# Buck_Converter.net
KiCad netlist of a schematic drawn in Altium Designer
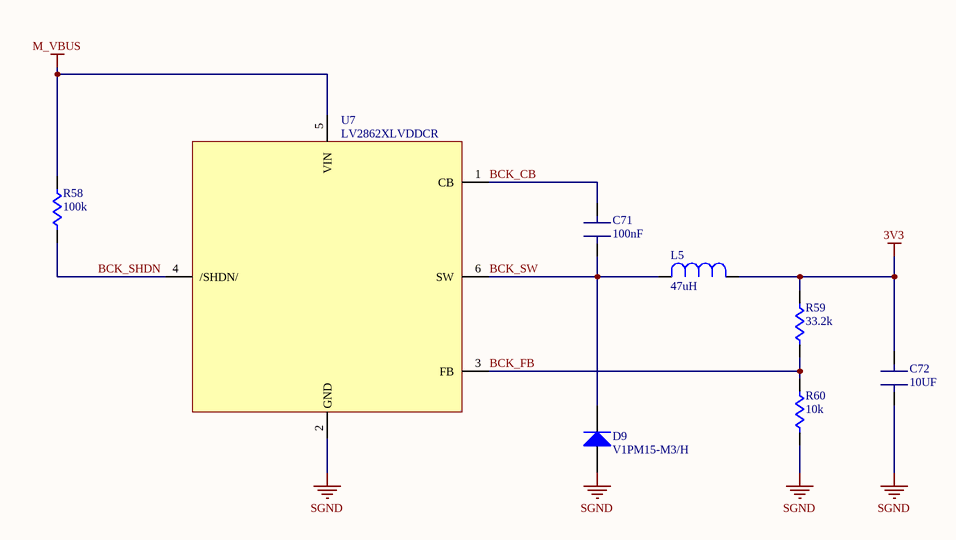
[diagram p0: Buck_Converter.SchDoc]

(export (version "E")
  (design (tool "Eeschema 10.0.6"))
  (components
    (comp (ref "C71")
      (value "100nF")
      (footprint "CAP: 0603")
      (description "CAP SMD 0603")
      (libsource (lib "HZSchLib") (part "CAP 0603"))
    )
    (comp (ref "C72")
      (value "10UF")
      (footprint "CAP: 0805")
      (description "CAP SMD 0805")
      (libsource (lib "HZSchLib") (part "CAP 0805"))
    )
    (comp (ref "D9")
      (value "V1PM15-M3/H")
      (footprint "DO-219AD-2")
      (description "Schottky Diodes & Rectifiers 150V 1A TMBS MicroSMP")
      (libsource (lib "HZSchLib") (part "V1PM15-M3/H"))
    )
    (comp (ref "L5")
      (value "47uH")
      (footprint "MDH6045C")
      (description "Power Inductors - SMD 47uH 208mOhms 20 % 1A AEC-Q200")
      (libsource (lib "HZSchLib") (part "MDH6045C-470MA=P3"))
    )
    (comp (ref "R58")
      (value "100k")
      (footprint "RES: 0603")
      (description "RES SMD 0603")
      (libsource (lib "HZSchLib") (part "RES 0603"))
    )
    (comp (ref "R59")
      (value "33.2k")
      (footprint "RES: 0603")
      (description "RES SMD 0603")
      (libsource (lib "HZSchLib") (part "RES 0603"))
    )
    (comp (ref "R60")
      (value "10k")
      (footprint "RES: 0603")
      (description "RES SMD 0603")
      (libsource (lib "HZSchLib") (part "RES 0603"))
    )
    (comp (ref "U7")
      (value "LV2862XLVDDCR")
      (footprint "SOT23-6")
      (description "Switching Voltage Regulators 4.5-V to 60-V 600-m A buck converter in A 595-LV2862XLVDDCT")
      (libsource (lib "HZSchLib") (part "LV2862XLVDDCR"))
    )
  )
  (nets
    (net (code "2") (name "/BCK_CB") (class "Default")
      (node (ref "C71") (pin "2") (pinfunction "B_2") (pintype "passive"))
      (node (ref "U7") (pin "1") (pinfunction "CB_1") (pintype "passive"))
    )
    (net (code "3") (name "/BCK_FB") (class "Default")
      (node (ref "R59") (pin "1") (pinfunction "1_1") (pintype "passive"))
      (node (ref "R60") (pin "2") (pinfunction "2_2") (pintype "passive"))
      (node (ref "U7") (pin "3") (pinfunction "FB_3") (pintype "passive"))
    )
    (net (code "4") (name "/BCK_SHDN") (class "Default")
      (node (ref "R58") (pin "1") (pinfunction "1_1") (pintype "passive"))
      (node (ref "U7") (pin "4") (pinfunction "/SHDN/_4") (pintype "power_in"))
    )
    (net (code "5") (name "/BCK_SW") (class "Default")
      (node (ref "C71") (pin "1") (pinfunction "A_1") (pintype "passive"))
      (node (ref "D9") (pin "1") (pinfunction "K_1") (pintype "passive"))
      (node (ref "L5") (pin "1") (pinfunction "1_1") (pintype "passive"))
      (node (ref "U7") (pin "6") (pinfunction "SW_6") (pintype "passive"))
    )
    (net (code "6") (name "3V3") (class "Default")
      (node (ref "C72") (pin "2") (pinfunction "B_2") (pintype "passive"))
      (node (ref "L5") (pin "2") (pinfunction "2_2") (pintype "passive"))
      (node (ref "R59") (pin "2") (pinfunction "2_2") (pintype "passive"))
    )
    (net (code "7") (name "M_VBUS") (class "Default")
      (node (ref "R58") (pin "2") (pinfunction "2_2") (pintype "passive"))
      (node (ref "U7") (pin "5") (pinfunction "VIN_5") (pintype "passive"))
    )
    (net (code "8") (name "SGND") (class "Default")
      (node (ref "C72") (pin "1") (pinfunction "A_1") (pintype "passive"))
      (node (ref "D9") (pin "2") (pinfunction "A_2") (pintype "passive"))
      (node (ref "R60") (pin "1") (pinfunction "1_1") (pintype "passive"))
      (node (ref "U7") (pin "2") (pinfunction "GND_2") (pintype "power_in"))
    )
  )
)
